# Rectenna.net
KiCad netlist of a schematic drawn in EasyEDA
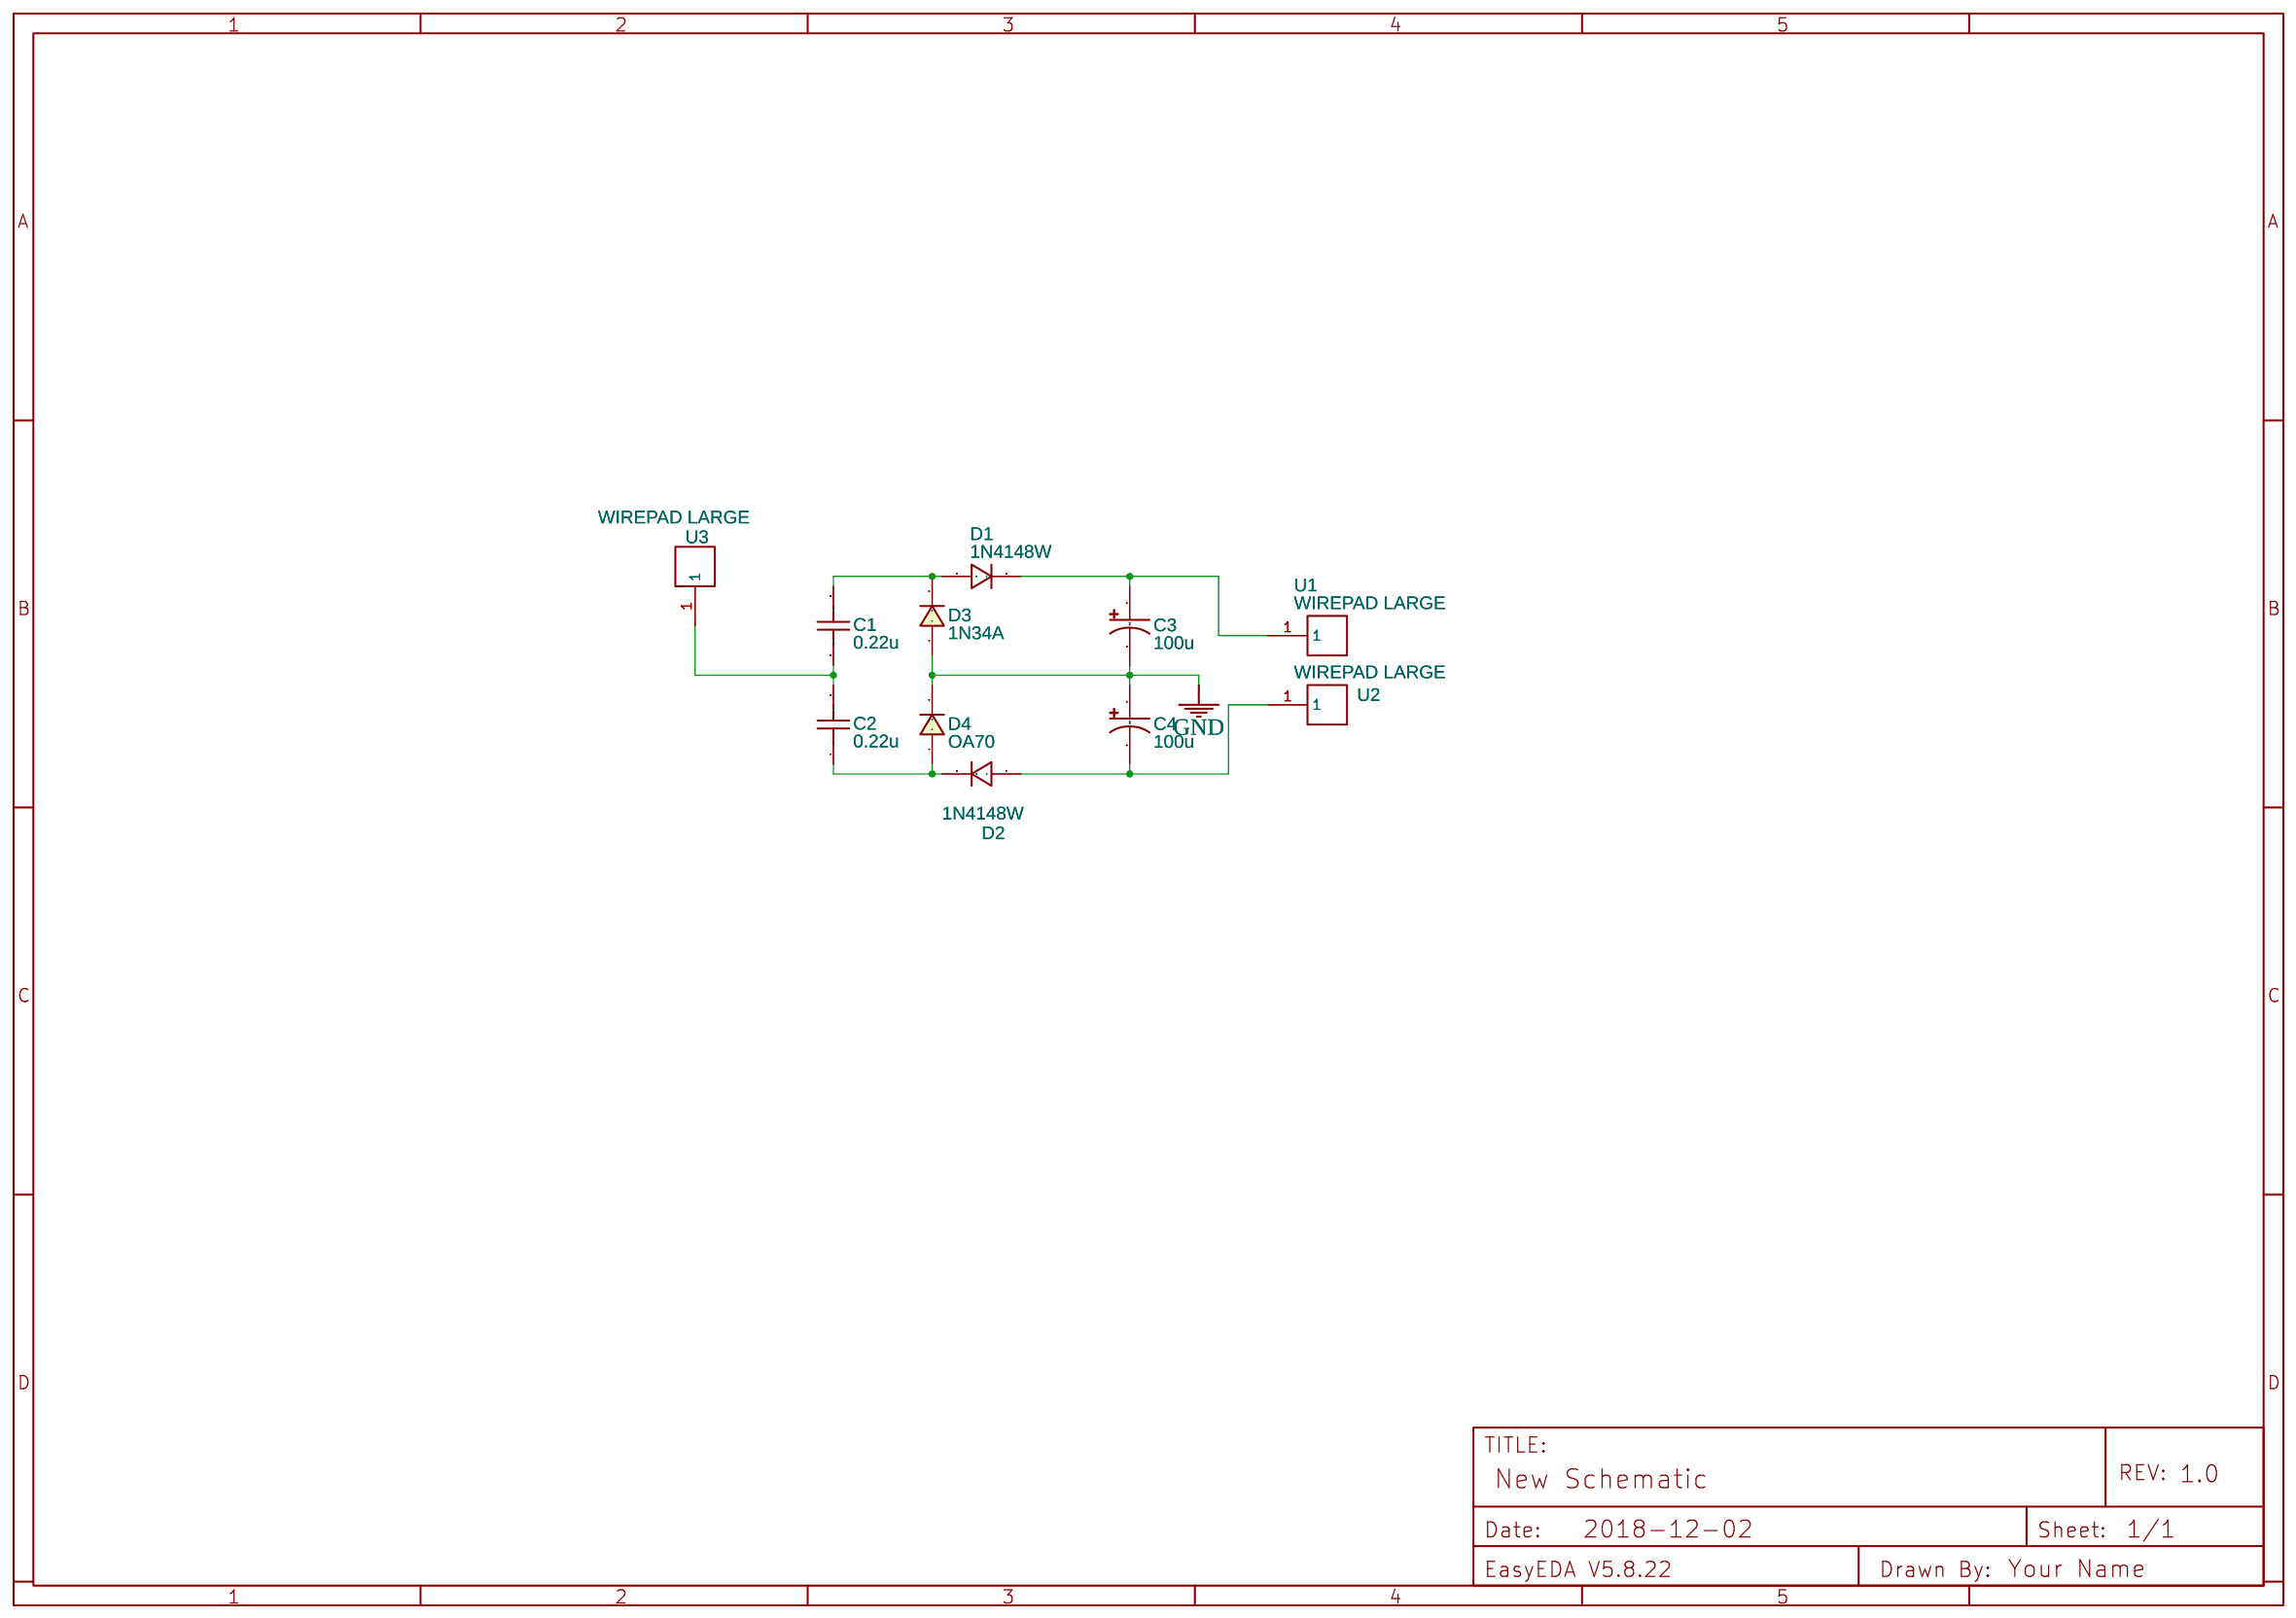
[diagram p0: schematic sheet]

(export (version "E")
  (design (tool "Eeschema 10.0.6"))
  (components
    (comp (ref "C1")
      (value "0.22u")
      (fields (field (name "BOM_Manufacturer Part") "?"))
      (libsource (lib "") (part "Cap_RAD-0.1_US"))
    )
    (comp (ref "C2")
      (value "0.22u")
      (fields (field (name "BOM_Manufacturer Part") "?"))
      (libsource (lib "") (part "Cap_RAD-0.1_US"))
    )
    (comp (ref "C3")
      (value "100u")
      (fields (field (name "BOM_Manufacturer Part") "?"))
      (libsource (lib "") (part "Cap_Electrolytic(TH)_D3.0XF1.5_US"))
    )
    (comp (ref "C4")
      (value "100u")
      (fields (field (name "BOM_Manufacturer Part") "?"))
      (libsource (lib "") (part "Cap_Electrolytic(TH)_D3.0XF1.5_US"))
    )
    (comp (ref "D1")
      (value "1N4148W")
      (fields (field (name "BOM_Supplier Part") "C81598"))
      (libsource (lib "") (part "Unknown_490_285"))
    )
    (comp (ref "D2")
      (value "1N4148W")
      (fields (field (name "BOM_Supplier Part") "C81598"))
      (libsource (lib "") (part "Unknown_490_385"))
    )
    (comp (ref "D3") (value "1N34A") (libsource (lib "") (part "Unknown_455_305")))
    (comp (ref "D4")
      (value "OA70")
      (fields (field (name "BOM_Manufacturer Part") "1N34A"))
      (libsource (lib "") (part "Unknown_455_360"))
    )
    (comp (ref "U1") (value "WIREPAD LARGE") (libsource (lib "") (part "Unknown_655_315")))
    (comp (ref "U2") (value "WIREPAD LARGE") (libsource (lib "") (part "Unknown_655_350")))
    (comp (ref "U3") (value "WIREPAD LARGE") (libsource (lib "") (part "Unknown_345_290")))
  )
  (nets
    (net (code "1") (name "GND") (class "Default")
      (node (ref "C3") (pin "2") (pinfunction "2_2") (pintype "unspecified"))
      (node (ref "C4") (pin "1") (pinfunction "1_1") (pintype "unspecified"))
      (node (ref "D3") (pin "1") (pinfunction "A_1") (pintype "unspecified"))
      (node (ref "D4") (pin "2") (pinfunction "K_2") (pintype "unspecified"))
    )
    (net (code "2") (name "Net-(C1-Pad1)") (class "Default")
      (node (ref "C1") (pin "1") (pinfunction "1_1") (pintype "unspecified"))
      (node (ref "C2") (pin "2") (pinfunction "2_2") (pintype "unspecified"))
      (node (ref "U3") (pin "1") (pinfunction "1_1") (pintype "unspecified"))
    )
    (net (code "3") (name "Net-(D1-A)") (class "Default")
      (node (ref "C1") (pin "2") (pinfunction "2_2") (pintype "unspecified"))
      (node (ref "D1") (pin "1") (pinfunction "A_1") (pintype "unspecified"))
      (node (ref "D3") (pin "2") (pinfunction "K_2") (pintype "unspecified"))
    )
    (net (code "4") (name "Net-(D1-K)") (class "Default")
      (node (ref "C3") (pin "1") (pinfunction "1_1") (pintype "unspecified"))
      (node (ref "D1") (pin "2") (pinfunction "K_2") (pintype "unspecified"))
      (node (ref "U1") (pin "1") (pinfunction "1_1") (pintype "unspecified"))
    )
    (net (code "5") (name "Net-(D2-A)") (class "Default")
      (node (ref "C4") (pin "2") (pinfunction "2_2") (pintype "unspecified"))
      (node (ref "D2") (pin "1") (pinfunction "A_1") (pintype "unspecified"))
      (node (ref "U2") (pin "1") (pinfunction "1_1") (pintype "unspecified"))
    )
    (net (code "6") (name "Net-(D2-K)") (class "Default")
      (node (ref "C2") (pin "1") (pinfunction "1_1") (pintype "unspecified"))
      (node (ref "D2") (pin "2") (pinfunction "K_2") (pintype "unspecified"))
      (node (ref "D4") (pin "1") (pinfunction "A_1") (pintype "unspecified"))
    )
  )
)
